# PackVoltageCurrentSensor.net
KiCad netlist of a schematic drawn in Altium Designer
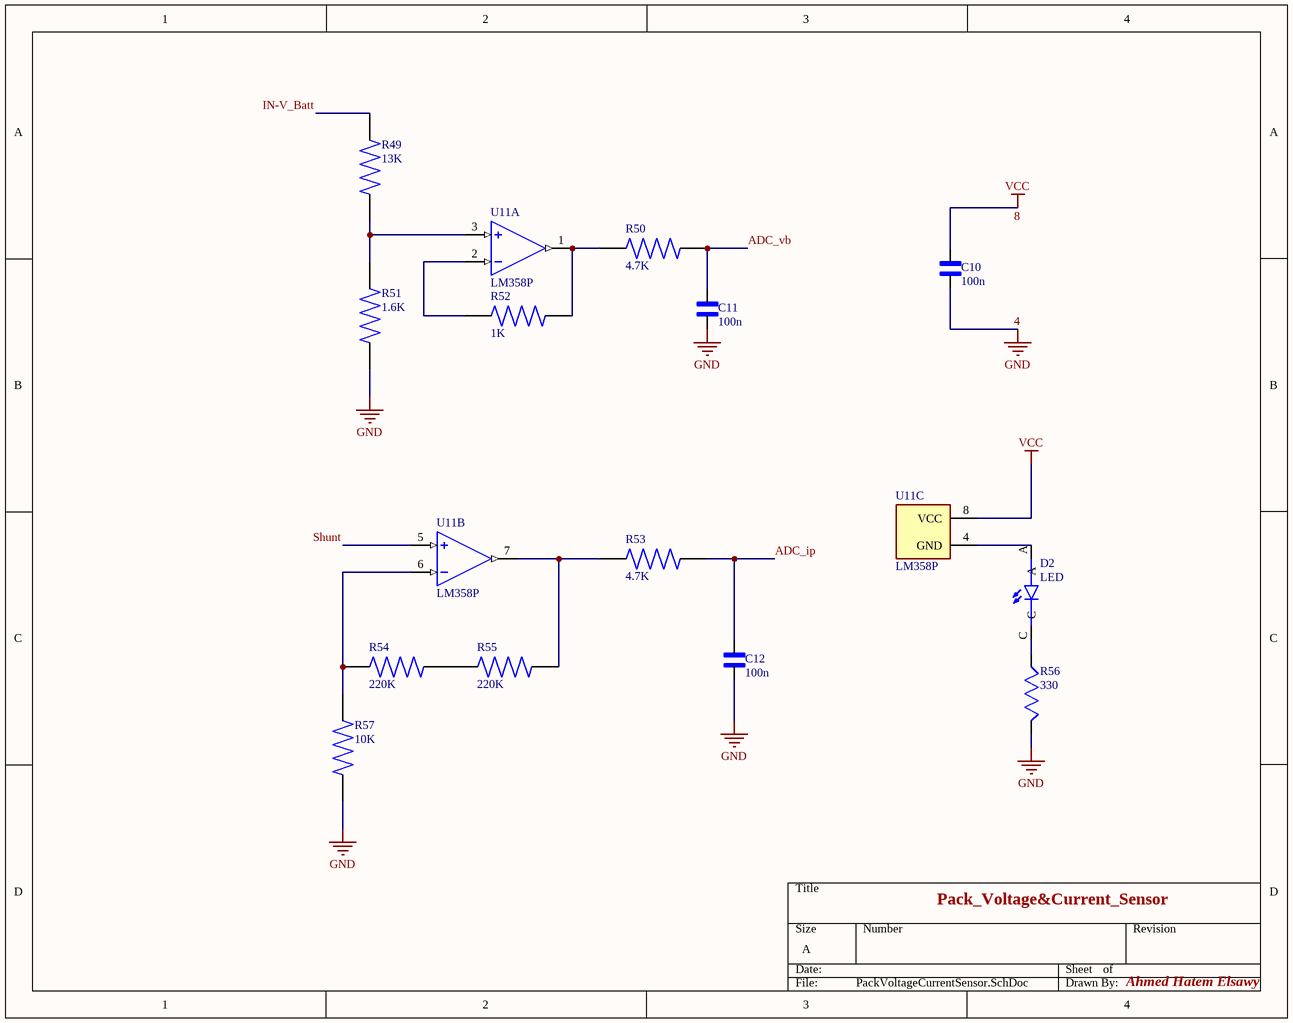
[diagram p0: PackVoltageCurrentSensor.SchDoc]

(export (version "E")
  (design (tool "Eeschema 10.0.6"))
  (components
    (comp (ref "C10")
      (value "100n")
      (footprint "CAPC1608X90N")
      (description "Capacitor MLCC 0603 100nF 50V ¦ AVX 06035C104K4T2A")
      (fields (field (name "MF") "AVX") (field (name "MP") "06035C104K4T2A"))
      (libsource (lib "06035C104K4T2A") (part "06035C104K4T2A"))
    )
    (comp (ref "C11")
      (value "100n")
      (footprint "CAPC1608X90N")
      (description "Capacitor MLCC 0603 100nF 50V ¦ AVX 06035C104K4T2A")
      (fields (field (name "MF") "AVX") (field (name "MP") "06035C104K4T2A"))
      (libsource (lib "06035C104K4T2A") (part "06035C104K4T2A"))
    )
    (comp (ref "C12")
      (value "100n")
      (footprint "CAPC1608X90N")
      (description "Capacitor MLCC 0603 100nF 50V ¦ AVX 06035C104K4T2A")
      (fields (field (name "MF") "AVX") (field (name "MP") "06035C104K4T2A"))
      (libsource (lib "06035C104K4T2A") (part "06035C104K4T2A"))
    )
    (comp (ref "D2")
      (value "LED")
      (footprint "LED_WP7113ID")
      (description "Red 617nm LED Indication - Discrete 2V Radial")
      (fields (field (name "MP") "WP7113ID") (field (name "MF") "Kingbright"))
      (libsource (lib "WP7113ID") (part "WP7113ID"))
    )
    (comp (ref "R49")
      (value "13K")
      (footprint "RES_ERJU03J133V")
      (description "RES 13K OHM 5% 1/10W 0603 SMD")
      (fields (field (name "MF") "Panasonic") (field (name "MP") "ERJ-U03J133V"))
      (libsource (lib "ERJU03J133V") (part "ERJU03J133V"))
    )
    (comp (ref "R50")
      (value "4.7K")
      (footprint "RES_ERJS06J472V")
      (fields (field (name "MP") "ERJS06J472V"))
      (libsource (lib "ERJS06J472V") (part "ERJS06J472V"))
    )
    (comp (ref "R51")
      (value "1.6K")
      (footprint "RES_ERA6ARB162V")
      (fields (field (name "MP") "ERA6ARB162V"))
      (libsource (lib "ERA6ARB162V") (part "ERA6ARB162V"))
    )
    (comp (ref "R52")
      (value "1K")
      (footprint "RESC1608X55N")
      (description "DirenÃ§, AS 0603 1k %1 100mW TC100 ¦ Bourns CR0603AFX-1001EAS")
      (fields (field (name "MF") "Bourns") (field (name "MP") "CR0603AFX-1001EAS"))
      (libsource (lib "CR0603AFX-1001EAS") (part "CR0603AFX-1001EAS"))
    )
    (comp (ref "R53")
      (value "4.7K")
      (footprint "RES_ERJS06J472V")
      (fields (field (name "MP") "ERJS06J472V"))
      (libsource (lib "ERJS06J472V") (part "ERJS06J472V"))
    )
    (comp (ref "R54")
      (value "220K")
      (footprint "RES_ERJS06J224V")
      (fields (field (name "MP") "ERJS06J224V"))
      (libsource (lib "ERJS06J224V") (part "ERJS06J224V"))
    )
    (comp (ref "R55")
      (value "220K")
      (footprint "RES_ERJS06J224V")
      (fields (field (name "MP") "ERJS06J224V"))
      (libsource (lib "ERJS06J224V") (part "ERJS06J224V"))
    )
    (comp (ref "R56")
      (value "330")
      (footprint "RESC3216X65")
      (description "Res Thick Film 1206 330 Ohm 5% 0.25W(1/4W) Â±100ppm/Â°C Epoxy Pad SMD T/R")
      (fields (field (name "MF") "Yageo Corporation") (field (name "MP") "RC1206JR13330RL"))
      (libsource (lib "RC1206JR-13330RL") (part "RC1206JR-13330RL"))
    )
    (comp (ref "R57")
      (value "10K")
      (footprint "RES_ERA8ARW103V")
      (fields (field (name "MP") "ERA8ARW103V"))
      (libsource (lib "ERA8ARW103V") (part "ERA8ARW103V"))
    )
    (comp (ref "U11")
      (value "LM358P")
      (footprint "DIP794W45P254L959H508Q8")
      (description "Dual, 30-V, 700-kHz operational amplifier")
      (fields (field (name "MF") "Texas Instruments"))
      (libsource (lib "LM358P") (part "LM358P"))
    )
  )
  (nets
    (net (code "1") (name "/ADC_ip") (class "Default")
      (node (ref "C12") (pin "1") (pinfunction "1_1") (pintype "passive"))
      (node (ref "R53") (pin "2") (pinfunction "2_2") (pintype "passive"))
    )
    (net (code "2") (name "/ADC_vb") (class "Default")
      (node (ref "C11") (pin "1") (pinfunction "1_1") (pintype "passive"))
      (node (ref "R50") (pin "2") (pinfunction "2_2") (pintype "passive"))
    )
    (net (code "3") (name "/IN-V_Batt") (class "Default")
      (node (ref "R49") (pin "2") (pinfunction "2_2") (pintype "passive"))
    )
    (net (code "4") (name "/Shunt") (class "Default")
      (node (ref "U11") (pin "5") (pinfunction "+IN2_5") (pintype "input"))
    )
    (net (code "5") (name "GND") (class "Default")
      (node (ref "C10") (pin "2") (pinfunction "2_2") (pintype "passive"))
      (node (ref "C11") (pin "2") (pinfunction "2_2") (pintype "passive"))
      (node (ref "C12") (pin "2") (pinfunction "2_2") (pintype "passive"))
      (node (ref "R51") (pin "1") (pinfunction "1_1") (pintype "passive"))
      (node (ref "R56") (pin "1") (pinfunction "1_1") (pintype "passive"))
      (node (ref "R57") (pin "1") (pinfunction "1_1") (pintype "passive"))
    )
    (net (code "6") (name "Net-(D2-PadC)") (class "Default")
      (node (ref "D2") (pin "C") (pinfunction "C_C") (pintype "passive"))
      (node (ref "R56") (pin "2") (pinfunction "2_2") (pintype "passive"))
    )
    (net (code "7") (name "Net-(R54-Pad2)") (class "Default")
      (node (ref "R54") (pin "2") (pinfunction "2_2") (pintype "passive"))
      (node (ref "R55") (pin "1") (pinfunction "1_1") (pintype "passive"))
    )
    (net (code "8") (name "Net-(U11A-+IN1)") (class "Default")
      (node (ref "R49") (pin "1") (pinfunction "1_1") (pintype "passive"))
      (node (ref "R51") (pin "2") (pinfunction "2_2") (pintype "passive"))
      (node (ref "U11") (pin "3") (pinfunction "+IN1_3") (pintype "input"))
    )
    (net (code "9") (name "Net-(U11A--IN1)") (class "Default")
      (node (ref "R52") (pin "1") (pinfunction "1_1") (pintype "passive"))
      (node (ref "U11") (pin "2") (pinfunction "-IN1_2") (pintype "input"))
    )
    (net (code "10") (name "Net-(U11A-OUT1)") (class "Default")
      (node (ref "R50") (pin "1") (pinfunction "1_1") (pintype "passive"))
      (node (ref "R52") (pin "2") (pinfunction "2_2") (pintype "passive"))
      (node (ref "U11") (pin "1") (pinfunction "OUT1_1") (pintype "output"))
    )
    (net (code "11") (name "Net-(U11B--IN2)") (class "Default")
      (node (ref "R54") (pin "1") (pinfunction "1_1") (pintype "passive"))
      (node (ref "R57") (pin "2") (pinfunction "2_2") (pintype "passive"))
      (node (ref "U11") (pin "6") (pinfunction "-IN2_6") (pintype "input"))
    )
    (net (code "12") (name "Net-(U11B-OUT2)") (class "Default")
      (node (ref "R53") (pin "1") (pinfunction "1_1") (pintype "passive"))
      (node (ref "R55") (pin "2") (pinfunction "2_2") (pintype "passive"))
      (node (ref "U11") (pin "7") (pinfunction "OUT2_7") (pintype "output"))
    )
    (net (code "13") (name "Net-(U11C-GND)") (class "Default")
      (node (ref "D2") (pin "A") (pinfunction "A_A") (pintype "passive"))
      (node (ref "U11") (pin "4") (pinfunction "GND_4") (pintype "power_in"))
    )
    (net (code "14") (name "VCC") (class "Default")
      (node (ref "C10") (pin "1") (pinfunction "1_1") (pintype "passive"))
      (node (ref "U11") (pin "8") (pinfunction "VCC_8") (pintype "power_in"))
    )
  )
)
